# MCU_board_in_foot_v2.net
KiCad netlist of a schematic drawn in EAGLE
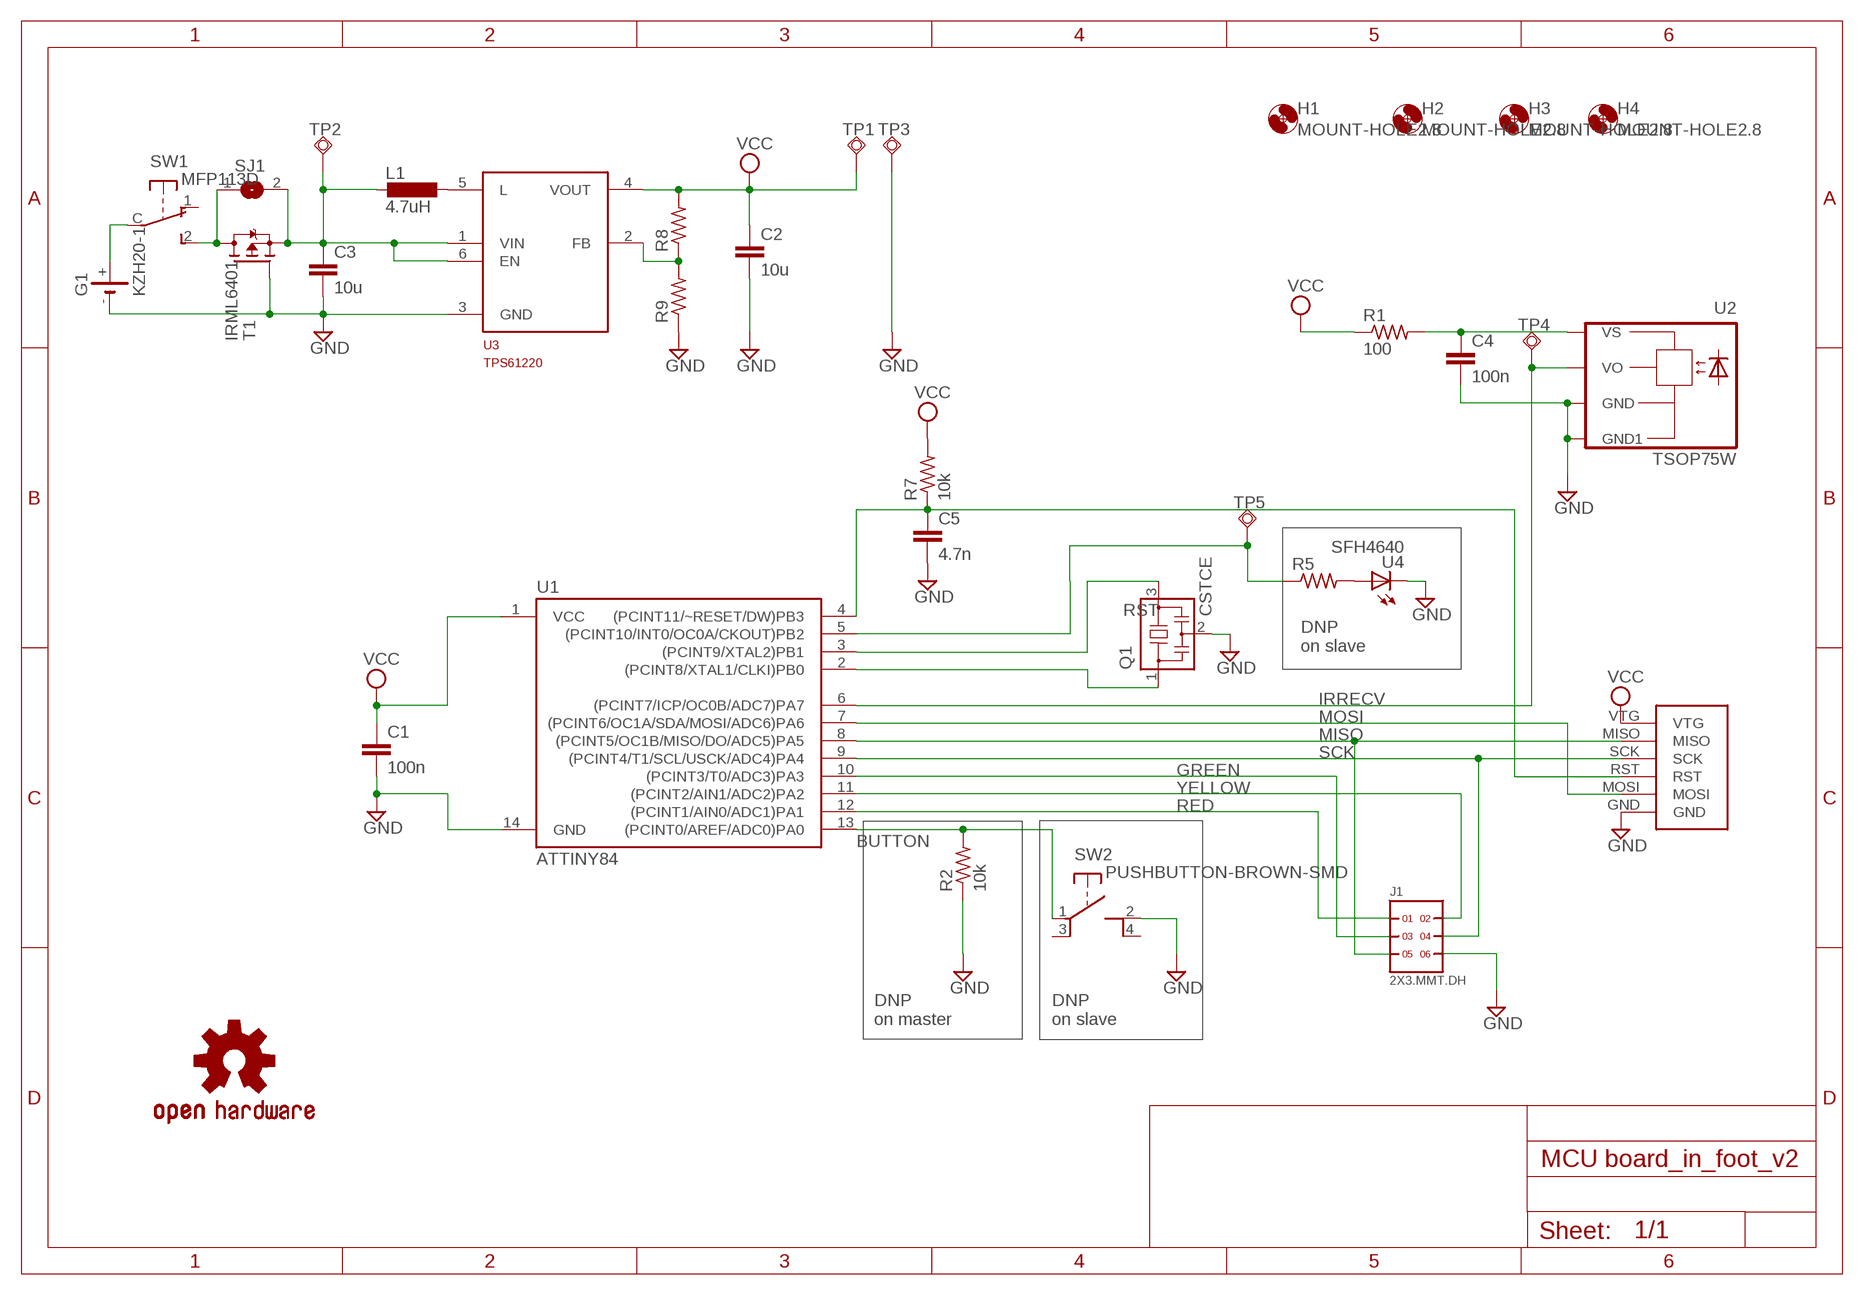
[diagram p0: schematic, sheet 1]

(export (version "E")
  (design (tool "Eeschema 10.0.6"))
  (components
    (comp (ref "C1")
      (value "100n")
      (footprint "eagle-import:0603-CAP")
      (libsource (lib "eagle-import") (part "CAP0603-CAP"))
    )
    (comp (ref "C2")
      (value "10u")
      (footprint "eagle-import:0603-CAP")
      (libsource (lib "eagle-import") (part "CAP0603-CAP"))
    )
    (comp (ref "C3")
      (value "10u")
      (footprint "eagle-import:0603-CAP")
      (libsource (lib "eagle-import") (part "MCU board_in_foot_99087_CAP0603-CAP"))
    )
    (comp (ref "C4")
      (value "100n")
      (footprint "eagle-import:0603-CAP")
      (libsource (lib "eagle-import") (part "CAP0603-CAP"))
    )
    (comp (ref "C5")
      (value "4.7n")
      (footprint "eagle-import:0603-CAP")
      (libsource (lib "eagle-import") (part "MCU board_in_foot_99087_CAP0603-CAP"))
    )
    (comp (ref "G1")
      (value "KZH20-1")
      (footprint "eagle-import:KZH20-1")
      (libsource (lib "eagle-import") (part "KZH20-1"))
    )
    (comp (ref "H1")
      (value "MOUNT-HOLE2.8")
      (footprint "eagle-import:2,8")
      (libsource (lib "eagle-import") (part "MCU board_in_foot_99087_MOUNT-HOLE2.8"))
    )
    (comp (ref "H2")
      (value "MOUNT-HOLE2.8")
      (footprint "eagle-import:2,8")
      (libsource (lib "eagle-import") (part "MOUNT-HOLE2.8"))
    )
    (comp (ref "H3")
      (value "MOUNT-HOLE2.8")
      (footprint "eagle-import:2,8")
      (libsource (lib "eagle-import") (part "MOUNT-HOLE2.8"))
    )
    (comp (ref "H4")
      (value "MOUNT-HOLE2.8")
      (footprint "eagle-import:2,8")
      (libsource (lib "eagle-import") (part "MCU board_in_foot_99087_MOUNT-HOLE2.8"))
    )
    (comp (ref "ISP")
      (value "ISP_POGOSURFACE")
      (footprint "eagle-import:ISP_SURFACE")
      (libsource (lib "eagle-import") (part "ISP_POGOSURFACE"))
    )
    (comp (ref "J1")
      (value "2X3.MMT.DH")
      (footprint "eagle-import:2X3_MMT.103.01.X.DH")
      (libsource (lib "eagle-import") (part "2X3.MMT.DH"))
    )
    (comp (ref "L1")
      (value "4.7uH")
      (footprint "eagle-import:EPL2010")
      (libsource (lib "eagle-import") (part "EPL2010"))
    )
    (comp (ref "LOGO1")
      (value "OSHW-LOGOS")
      (footprint "eagle-import:OSHW-LOGO-S")
      (libsource (lib "eagle-import") (part "OSHW-LOGOS"))
    )
    (comp (ref "Q1")
      (value "CSTCE")
      (footprint "eagle-import:CSTCE")
      (libsource (lib "eagle-import") (part "CSTCE"))
    )
    (comp (ref "R1")
      (value "100")
      (footprint "eagle-import:R0603")
      (libsource (lib "eagle-import") (part "R-US_R0603"))
    )
    (comp (ref "R2")
      (value "10k")
      (footprint "eagle-import:R0603")
      (libsource (lib "eagle-import") (part "R-US_R0603"))
    )
    (comp (ref "R5")
      (value "R-US_R0603")
      (footprint "eagle-import:R0603")
      (libsource (lib "eagle-import") (part "R-US_R0603"))
    )
    (comp (ref "R7")
      (value "10k")
      (footprint "eagle-import:R0603")
      (libsource (lib "eagle-import") (part "R-US_R0603"))
    )
    (comp (ref "R8")
      (value "R-US_R0603")
      (footprint "eagle-import:R0603")
      (libsource (lib "eagle-import") (part "R-US_R0603"))
    )
    (comp (ref "R9")
      (value "R-US_R0603")
      (footprint "eagle-import:R0603")
      (libsource (lib "eagle-import") (part "R-US_R0603"))
    )
    (comp (ref "SJ1") (value "SJ") (footprint "eagle-import:SJ") (libsource (lib "eagle-import") (part "SJ")))
    (comp (ref "SW1")
      (value "MFP113D")
      (footprint "eagle-import:MFP-SLIDER")
      (libsource (lib "eagle-import") (part "MFP113D"))
    )
    (comp (ref "SW2")
      (value "PUSHBUTTON-BROWN-SMD")
      (footprint "eagle-import:SMD-SW")
      (libsource (lib "eagle-import") (part "PUSHBUTTON-BROWN-SMD"))
    )
    (comp (ref "T1")
      (value "IRML6401")
      (footprint "eagle-import:SOT23")
      (libsource (lib "eagle-import") (part "IRML6401"))
    )
    (comp (ref "TP1")
      (value "TPSQTP20SQTH")
      (footprint "eagle-import:TP20SQTH")
      (libsource (lib "eagle-import") (part "TPSQTP20SQTH"))
    )
    (comp (ref "TP2")
      (value "TPSQTP20SQTH")
      (footprint "eagle-import:TP20SQTH")
      (libsource (lib "eagle-import") (part "TPSQTP20SQTH"))
    )
    (comp (ref "TP3")
      (value "TPSQTP20SQTH")
      (footprint "eagle-import:TP20SQTH")
      (libsource (lib "eagle-import") (part "TPSQTP20SQTH"))
    )
    (comp (ref "TP4")
      (value "TPSQTP20SQTH")
      (footprint "eagle-import:TP20SQTH")
      (libsource (lib "eagle-import") (part "TPSQTP20SQTH"))
    )
    (comp (ref "TP5")
      (value "TPSQTP20SQTH")
      (footprint "eagle-import:TP20SQTH")
      (libsource (lib "eagle-import") (part "TPSQTP20SQTH"))
    )
    (comp (ref "U1")
      (value "ATTINY84")
      (footprint "eagle-import:SO14")
      (libsource (lib "eagle-import") (part "ATTINY84"))
    )
    (comp (ref "U2")
      (value "TSOP75W")
      (footprint "eagle-import:TSOP75W-SIDELOOK")
      (libsource (lib "eagle-import") (part "TSOP75W"))
    )
    (comp (ref "U3")
      (value "TPS61220")
      (footprint "eagle-import:DCK-R_PDSO_G6")
      (libsource (lib "eagle-import") (part "TPS61220"))
    )
    (comp (ref "U4")
      (value "SFH4640")
      (footprint "eagle-import:MIDLED")
      (libsource (lib "eagle-import") (part "SFH4640"))
    )
  )
  (nets
    (net (code "1") (name "/BUTTON") (class "Default")
      (node (ref "R2") (pin "2") (pinfunction "2_2") (pintype "passive"))
      (node (ref "SW2") (pin "1") (pinfunction "P1_1") (pintype "passive"))
      (node (ref "U1") (pin "13") (pinfunction "(PCINT0/AREF/ADC0)PA0_13") (pintype "bidirectional"))
    )
    (net (code "2") (name "/GREEN") (class "Default")
      (node (ref "J1") (pin "3") (pinfunction "3_3") (pintype "bidirectional"))
      (node (ref "U1") (pin "10") (pinfunction "(PCINT3/T0/ADC3)PA3_10") (pintype "bidirectional"))
    )
    (net (code "3") (name "/IRRECV") (class "Default")
      (node (ref "TP4") (pin "TP") (pinfunction "TP_TP") (pintype "input"))
      (node (ref "U1") (pin "6") (pinfunction "(PCINT7/ICP/OC0B/ADC7)PA7_6") (pintype "bidirectional"))
      (node (ref "U2") (pin "3") (pinfunction "VO_3") (pintype "open_collector"))
    )
    (net (code "4") (name "/MISO") (class "Default")
      (node (ref "ISP") (pin "MISO") (pinfunction "MISO_MISO") (pintype "bidirectional"))
      (node (ref "J1") (pin "5") (pinfunction "5_5") (pintype "bidirectional"))
      (node (ref "U1") (pin "8") (pinfunction "(PCINT5/OC1B/MISO/DO/ADC5)PA5_8") (pintype "bidirectional"))
    )
    (net (code "5") (name "/MOSI") (class "Default")
      (node (ref "ISP") (pin "MOSI") (pinfunction "MOSI_MOSI") (pintype "bidirectional"))
      (node (ref "U1") (pin "7") (pinfunction "(PCINT6/OC1A/SDA/MOSI/ADC6)PA6_7") (pintype "bidirectional"))
    )
    (net (code "6") (name "/RED") (class "Default")
      (node (ref "J1") (pin "1") (pinfunction "1_1") (pintype "bidirectional"))
      (node (ref "U1") (pin "12") (pinfunction "(PCINT1/AIN0/ADC1)PA1_12") (pintype "bidirectional"))
    )
    (net (code "7") (name "/RST") (class "Default")
      (node (ref "C5") (pin "1") (pinfunction "1_1") (pintype "passive"))
      (node (ref "ISP") (pin "RST") (pinfunction "RST_RST") (pintype "bidirectional"))
      (node (ref "R7") (pin "1") (pinfunction "1_1") (pintype "passive"))
      (node (ref "U1") (pin "4") (pinfunction "(PCINT11/~{RESET/DW})PB3_4") (pintype "bidirectional"))
    )
    (net (code "8") (name "/SCK") (class "Default")
      (node (ref "ISP") (pin "SCK") (pinfunction "SCK_SCK") (pintype "bidirectional"))
      (node (ref "J1") (pin "4") (pinfunction "4_4") (pintype "bidirectional"))
      (node (ref "U1") (pin "9") (pinfunction "(PCINT4/T1/SCL/USCK/ADC4)PA4_9") (pintype "bidirectional"))
    )
    (net (code "9") (name "/YELLOW") (class "Default")
      (node (ref "J1") (pin "2") (pinfunction "2_2") (pintype "bidirectional"))
      (node (ref "U1") (pin "11") (pinfunction "(PCINT2/AIN1/ADC2)PA2_11") (pintype "bidirectional"))
    )
    (net (code "10") (name "GND") (class "Default")
      (node (ref "C1") (pin "2") (pinfunction "2_2") (pintype "passive"))
      (node (ref "C2") (pin "2") (pinfunction "2_2") (pintype "passive"))
      (node (ref "C3") (pin "2") (pinfunction "2_2") (pintype "passive"))
      (node (ref "C4") (pin "2") (pinfunction "2_2") (pintype "passive"))
      (node (ref "C5") (pin "2") (pinfunction "2_2") (pintype "passive"))
      (node (ref "G1") (pin "-") (pinfunction "-_-") (pintype "passive"))
      (node (ref "ISP") (pin "GND") (pinfunction "GND_GND") (pintype "bidirectional"))
      (node (ref "J1") (pin "6") (pinfunction "6_6") (pintype "bidirectional"))
      (node (ref "Q1") (pin "2") (pinfunction "2_2") (pintype "passive"))
      (node (ref "R2") (pin "1") (pinfunction "1_1") (pintype "passive"))
      (node (ref "R9") (pin "1") (pinfunction "1_1") (pintype "passive"))
      (node (ref "SW2") (pin "2") (pinfunction "S2_2") (pintype "passive"))
      (node (ref "T1") (pin "1") (pinfunction "G_1") (pintype "passive"))
      (node (ref "TP3") (pin "TP") (pinfunction "TP_TP") (pintype "input"))
      (node (ref "U1") (pin "14") (pinfunction "GND_14") (pintype "bidirectional"))
      (node (ref "U2") (pin "1") (pinfunction "GND_1") (pintype "power_in"))
      (node (ref "U2") (pin "4") (pinfunction "GND1_4") (pintype "power_in"))
      (node (ref "U3") (pin "3") (pinfunction "GND_3") (pintype "bidirectional"))
      (node (ref "U4") (pin "K") (pinfunction "C_K") (pintype "passive"))
    )
    (net (code "11") (name "Net-(L1-1)") (class "Default")
      (node (ref "C3") (pin "1") (pinfunction "1_1") (pintype "passive"))
      (node (ref "L1") (pin "P$1") (pinfunction "1_P$1") (pintype "passive"))
      (node (ref "SJ1") (pin "2") (pinfunction "2_2") (pintype "passive"))
      (node (ref "T1") (pin "2") (pinfunction "S_2") (pintype "passive"))
      (node (ref "TP2") (pin "TP") (pinfunction "TP_TP") (pintype "input"))
      (node (ref "U3") (pin "1") (pinfunction "VIN_1") (pintype "bidirectional"))
      (node (ref "U3") (pin "6") (pinfunction "EN_6") (pintype "bidirectional"))
    )
    (net (code "12") (name "Net-(L1-2)") (class "Default")
      (node (ref "L1") (pin "P$2") (pinfunction "2_P$2") (pintype "passive"))
      (node (ref "U3") (pin "5") (pinfunction "L_5") (pintype "bidirectional"))
    )
    (net (code "13") (name "Net-(R5-Pad2)") (class "Default")
      (node (ref "R5") (pin "2") (pinfunction "2_2") (pintype "passive"))
      (node (ref "U4") (pin "A") (pinfunction "A_A") (pintype "passive"))
    )
    (net (code "14") (name "Net-(SW1-P)") (class "Default")
      (node (ref "G1") (pin "+") (pinfunction "+_+") (pintype "passive"))
      (node (ref "SW1") (pin "C") (pinfunction "P_C") (pintype "passive"))
    )
    (net (code "15") (name "Net-(SW1-S)") (class "Default")
      (node (ref "SJ1") (pin "1") (pinfunction "1_1") (pintype "passive"))
      (node (ref "SW1") (pin "2") (pinfunction "S_2") (pintype "passive"))
      (node (ref "T1") (pin "3") (pinfunction "D_3") (pintype "passive"))
    )
    (net (code "16") (name "Net-(U1-(PCINT8{slash}XTAL1{slash}CLKI)PB0)") (class "Default")
      (node (ref "Q1") (pin "1") (pinfunction "1_1") (pintype "passive"))
      (node (ref "U1") (pin "2") (pinfunction "(PCINT8/XTAL1/CLKI)PB0_2") (pintype "bidirectional"))
    )
    (net (code "17") (name "Net-(U1-(PCINT9{slash}XTAL2)PB1)") (class "Default")
      (node (ref "Q1") (pin "3") (pinfunction "3_3") (pintype "passive"))
      (node (ref "U1") (pin "3") (pinfunction "(PCINT9/XTAL2)PB1_3") (pintype "bidirectional"))
    )
    (net (code "18") (name "Net-(U1-(PCINT10{slash}INT0{slash}OC0A{slash}CKOUT)PB2)") (class "Default")
      (node (ref "R5") (pin "1") (pinfunction "1_1") (pintype "passive"))
      (node (ref "TP5") (pin "TP") (pinfunction "TP_TP") (pintype "input"))
      (node (ref "U1") (pin "5") (pinfunction "(PCINT10/INT0/OC0A/CKOUT)PB2_5") (pintype "bidirectional"))
    )
    (net (code "19") (name "Net-(U2-VS)") (class "Default")
      (node (ref "C4") (pin "1") (pinfunction "1_1") (pintype "passive"))
      (node (ref "R1") (pin "2") (pinfunction "2_2") (pintype "passive"))
      (node (ref "U2") (pin "2") (pinfunction "VS_2") (pintype "power_in"))
    )
    (net (code "20") (name "Net-(U3-FB)") (class "Default")
      (node (ref "R8") (pin "1") (pinfunction "1_1") (pintype "passive"))
      (node (ref "R9") (pin "2") (pinfunction "2_2") (pintype "passive"))
      (node (ref "U3") (pin "2") (pinfunction "FB_2") (pintype "bidirectional"))
    )
    (net (code "21") (name "VCC") (class "Default")
      (node (ref "C1") (pin "1") (pinfunction "1_1") (pintype "passive"))
      (node (ref "C2") (pin "1") (pinfunction "1_1") (pintype "passive"))
      (node (ref "ISP") (pin "VTG") (pinfunction "VTG_VTG") (pintype "bidirectional"))
      (node (ref "R1") (pin "1") (pinfunction "1_1") (pintype "passive"))
      (node (ref "R7") (pin "2") (pinfunction "2_2") (pintype "passive"))
      (node (ref "R8") (pin "2") (pinfunction "2_2") (pintype "passive"))
      (node (ref "TP1") (pin "TP") (pinfunction "TP_TP") (pintype "input"))
      (node (ref "U1") (pin "1") (pinfunction "VCC_1") (pintype "bidirectional"))
      (node (ref "U3") (pin "4") (pinfunction "VOUT_4") (pintype "bidirectional"))
    )
    (net (code "22") (name "unconnected-(SW1-O-Pad1)") (class "Default")
      (node (ref "SW1") (pin "1") (pinfunction "O_1") (pintype "passive"))
    )
    (net (code "23") (name "unconnected-(SW2-P3-Pad3)") (class "Default")
      (node (ref "SW2") (pin "3") (pinfunction "P3_3") (pintype "passive"))
    )
    (net (code "24") (name "unconnected-(SW2-S4-Pad4)") (class "Default")
      (node (ref "SW2") (pin "4") (pinfunction "S4_4") (pintype "passive"))
    )
  )
)
